# TYPEB.net
KiCad netlist of a schematic drawn in Altium Designer
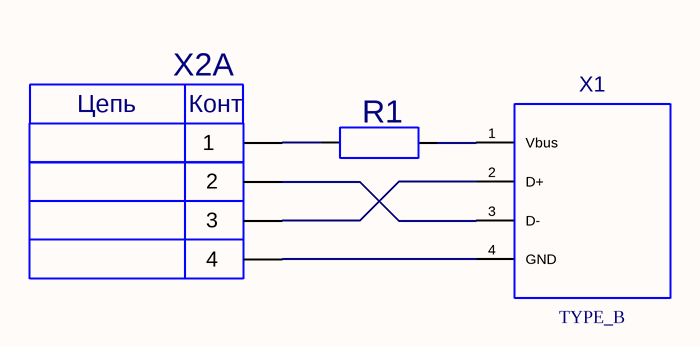
[diagram p0: TYPEB.SchDoc]

(export (version "E")
  (design (tool "Eeschema 10.0.6"))
  (components
    (comp (ref "R1")
      (value "0 Ом")
      (footprint "R1206H07")
      (description "Постоянный ЧИП резистор")
      (fields
        (field (name "PART NUMBER") "1206 0 Ом±5%")
        (field (name "POWER") "0.25W")
        (field (name "HELPURL") "D:\\Local_view\\PDM\\Справочники\\Перечень ЭРИ\\Документация\\Резисторы\\Постоянные\\ЧИП\\RC1206_yageo.pdf")
      )
      (libsource (lib "Library") (part "R"))
    )
    (comp (ref "X1")
      (value "TYPE_B")
      (footprint "Type_B")
      (description "USB_type_B")
      (fields
        (field (name "MANUFACTURER") "Texas Instruments")
        (field (name "VALUESCH") "TYPE_B")
        (field (name "COMPONENTLINK1URL") "c:\\Dataseets\\Микросхемы\\По фирмам\\Avago Technologies\\HCPL-4100.pdf")
      )
      (libsource (lib "nanoArduino") (part "USB_type_B"))
    )
    (comp (ref "X2")
      (value "PLS-04")
      (footprint "PLS-04")
      (description "Вилка на плату прямая шаг 2,54 мм 1 ряд")
      (fields
        (field (name "HELPURL") "D:\\Local_view\\PDM\\Справочники\\Перечень ЭРИ\\Документация\\Соединители\\Прямоугольные\\pld_pls.pdf")
      )
      (libsource (lib "Library") (part "CONT4"))
    )
  )
  (nets
    (net (code "1") (name "Net-(R1-Pad1)") (class "Default")
      (node (ref "R1") (pin "1") (pinfunction "1_1") (pintype "passive"))
      (node (ref "X2") (pin "1") (pinfunction "1_1") (pintype "passive"))
    )
    (net (code "2") (name "Net-(X1-D+)") (class "Default")
      (node (ref "X1") (pin "2") (pinfunction "D+_2") (pintype "passive"))
      (node (ref "X2") (pin "3") (pinfunction "3_3") (pintype "passive"))
    )
    (net (code "3") (name "Net-(X1-D-)") (class "Default")
      (node (ref "X1") (pin "3") (pinfunction "D-_3") (pintype "passive"))
      (node (ref "X2") (pin "2") (pinfunction "2_2") (pintype "passive"))
    )
    (net (code "4") (name "Net-(X1-GND)") (class "Default")
      (node (ref "X1") (pin "4") (pinfunction "GND_4") (pintype "passive"))
      (node (ref "X2") (pin "4") (pinfunction "4_4") (pintype "passive"))
    )
    (net (code "5") (name "Net-(X1-Vbus)") (class "Default")
      (node (ref "R1") (pin "2") (pinfunction "2_2") (pintype "passive"))
      (node (ref "X1") (pin "1") (pinfunction "Vbus_1") (pintype "passive"))
    )
  )
)
